# SN54LS145N_CommunicationInterface.net
KiCad netlist of a schematic drawn in Altium Designer
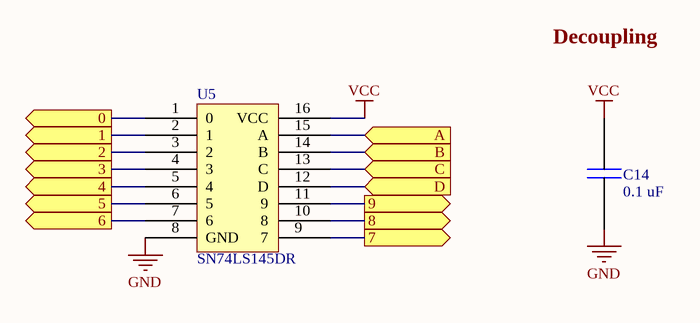
[diagram p0: SN54LS145N_CommunicationInterface.SchDoc]

(export (version "E")
  (design (tool "Eeschema 10.0.6"))
  (components
    (comp (ref "C14")
      (value "0.1 uF")
      (footprint "techdev:CAP0603")
      (description "Capacitores cerámicos de capas múltiples (MLCC) - SMD/SMT 0603 0.1uF 16volts X7R 5%")
      (fields (field (name "MPN") "VJ0603Y104JXJPW1BC") (field (name "Comment") "CAP0.1uF"))
      (libsource (lib "Miscellaneous Devices") (part "C0.1UF"))
    )
    (comp (ref "U5")
      (value "SN74LS145DR")
      (footprint "SOIC16")
      (description "Codificadores, decodificadores, multiplexores y demultiplexores BCD-To-Decimal Decoders/Drivers")
      (libsource (lib "Miscellaneous Devices") (part "SN74LS145DR"))
    )
  )
  (nets
    (net (code "1") (name "/0") (class "Default")
      (node (ref "U5") (pin "1") (pinfunction "0_1") (pintype "passive"))
    )
    (net (code "2") (name "/1") (class "Default")
      (node (ref "U5") (pin "2") (pinfunction "1_2") (pintype "passive"))
    )
    (net (code "3") (name "/2") (class "Default")
      (node (ref "U5") (pin "3") (pinfunction "2_3") (pintype "passive"))
    )
    (net (code "4") (name "/3") (class "Default")
      (node (ref "U5") (pin "4") (pinfunction "3_4") (pintype "passive"))
    )
    (net (code "5") (name "/4") (class "Default")
      (node (ref "U5") (pin "5") (pinfunction "4_5") (pintype "passive"))
    )
    (net (code "6") (name "/5") (class "Default")
      (node (ref "U5") (pin "6") (pinfunction "5_6") (pintype "passive"))
    )
    (net (code "7") (name "/6") (class "Default")
      (node (ref "U5") (pin "7") (pinfunction "6_7") (pintype "passive"))
    )
    (net (code "8") (name "/7") (class "Default")
      (node (ref "U5") (pin "9") (pinfunction "7_9") (pintype "passive"))
    )
    (net (code "9") (name "/8") (class "Default")
      (node (ref "U5") (pin "10") (pinfunction "8_10") (pintype "passive"))
    )
    (net (code "10") (name "/9") (class "Default")
      (node (ref "U5") (pin "11") (pinfunction "9_11") (pintype "passive"))
    )
    (net (code "11") (name "/A") (class "Default")
      (node (ref "U5") (pin "15") (pinfunction "A_15") (pintype "passive"))
    )
    (net (code "12") (name "/B") (class "Default")
      (node (ref "U5") (pin "14") (pinfunction "B_14") (pintype "passive"))
    )
    (net (code "13") (name "/C") (class "Default")
      (node (ref "U5") (pin "13") (pinfunction "C_13") (pintype "passive"))
    )
    (net (code "14") (name "/D") (class "Default")
      (node (ref "U5") (pin "12") (pinfunction "D_12") (pintype "passive"))
    )
    (net (code "16") (name "GND") (class "Default")
      (node (ref "C14") (pin "2") (pintype "passive"))
      (node (ref "U5") (pin "8") (pinfunction "GND_8") (pintype "passive"))
    )
    (net (code "17") (name "VCC") (class "Default")
      (node (ref "C14") (pin "1") (pintype "passive"))
      (node (ref "U5") (pin "16") (pinfunction "VCC_16") (pintype "passive"))
    )
  )
)
